# A-Headers.net
KiCad netlist of a schematic drawn in Altium Designer
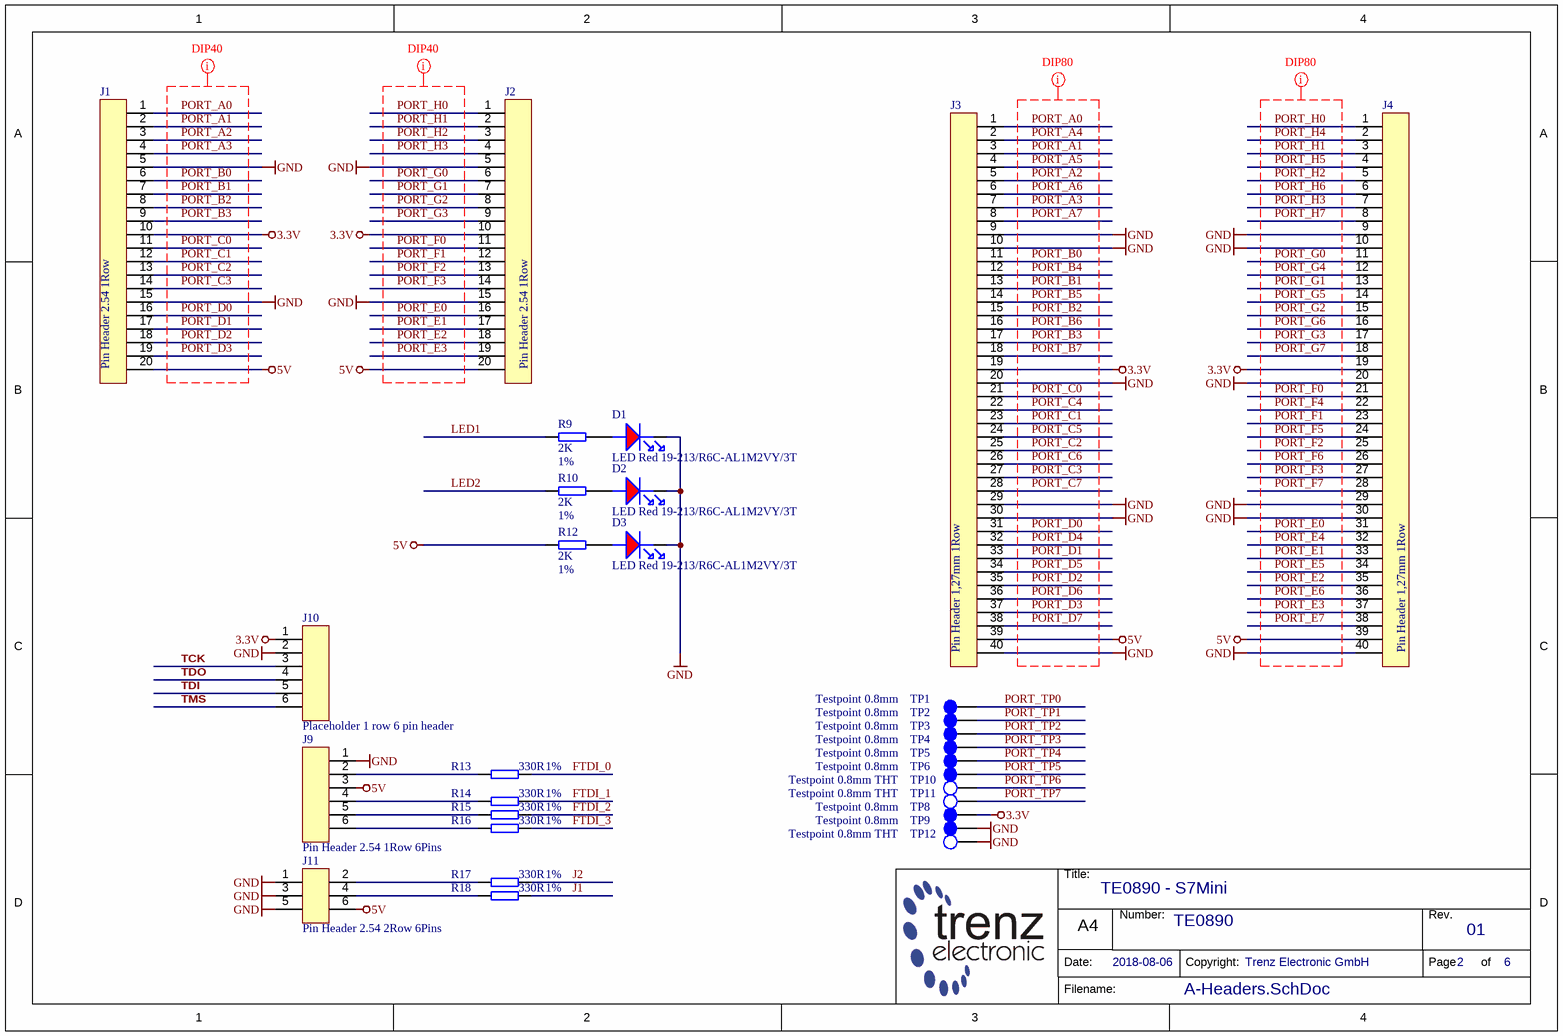
[diagram p0: A-Headers.SchDoc]

(export (version "E")
  (design (tool "Eeschema 10.0.6"))
  (components
    (comp (ref "D1")
      (value "LED Red 19-213/R6C-AL1M2VY/3T")
      (footprint "LEDC1608X55N_RED")
      (description "Chip LED 0603 Briliant Red")
      (libsource (lib "TE") (part "LED_ROT"))
    )
    (comp (ref "D2")
      (value "LED Red 19-213/R6C-AL1M2VY/3T")
      (footprint "LEDC1608X55N_RED")
      (description "Chip LED 0603 Briliant Red")
      (libsource (lib "TE") (part "LED_ROT"))
    )
    (comp (ref "D3")
      (value "LED Red 19-213/R6C-AL1M2VY/3T")
      (footprint "LEDC1608X55N_RED")
      (description "Chip LED 0603 Briliant Red")
      (libsource (lib "TE") (part "LED_ROT"))
    )
    (comp (ref "J1")
      (value "Pin Header 2.54 1Row")
      (footprint "STIFTLEISTE2_54 OG 1R-20")
      (description "Stiftleiste versetzt 1-reihig, 20pol.")
      (libsource (lib "") (part "CON-20_1"))
    )
    (comp (ref "J2")
      (value "Pin Header 2.54 1Row")
      (footprint "STIFTLEISTE2_54 OG 1R-20")
      (description "Stiftleiste versetzt 1-reihig, 20pol.")
      (libsource (lib "TE") (part "CON-20"))
    )
    (comp (ref "J3")
      (value "Pin Header 1,27mm 1Row")
      (footprint "STIFTLEISTE1_27 OG 1R-40")
      (description "Stiftleiste versetzt 1-reihig, 40pol.")
      (libsource (lib "") (part "CON-40_1"))
    )
    (comp (ref "J4")
      (value "Pin Header 1,27mm 1Row")
      (footprint "STIFTLEISTE1_27 OG 1R-40")
      (description "Stiftleiste versetzt 1-reihig, 40pol.")
      (libsource (lib "TE") (part "CON-40"))
    )
    (comp (ref "J9")
      (value "Pin Header 2.54 1Row 6Pins")
      (footprint "STIFTLEISTE2_54 OG 1R-6")
      (description "Stiftleiste gerade 1-reihig, 6pol")
      (libsource (lib "") (part "CON-6_1"))
    )
    (comp (ref "J10")
      (value "Placeholder 1 row 6 pin header")
      (footprint "STIFTLEISTE2_54 OG 1R-6V")
      (description "Stiftleiste versetzt 1-reihig, 6pol.")
      (libsource (lib "TE") (part "STIFTLEISTE2_54 OG 1R-6V"))
    )
    (comp (ref "J11")
      (value "Pin Header 2.54 2Row 6Pins")
      (footprint "STIFTLEISTE2_54 OG 2R-6")
      (description "Stiftleiste gerade 2-reihig, 6pol.")
      (libsource (lib "TE") (part "CON-6"))
    )
    (comp (ref "R9")
      (value "2K")
      (footprint "RESC1005X40N")
      (description "WID SMD 2K 1% 0,063W")
      (fields (field (name "TOLERANCE") "1%"))
      (libsource (lib "TE") (part "RES"))
    )
    (comp (ref "R10")
      (value "2K")
      (footprint "RESC1005X40N")
      (description "WID SMD 2K 1% 0,063W")
      (fields (field (name "TOLERANCE") "1%"))
      (libsource (lib "TE") (part "RES"))
    )
    (comp (ref "R12")
      (value "2K")
      (footprint "RESC1005X40N")
      (description "WID SMD 2K 1% 0,063W")
      (fields (field (name "TOLERANCE") "1%"))
      (libsource (lib "TE") (part "RES"))
    )
    (comp (ref "R13")
      (value "330R")
      (footprint "RESC1005X40N")
      (description "WID SMD 330R 1% 0,063W  BF 1005 (0402)")
      (fields (field (name "TOLERANCE") "1%"))
      (libsource (lib "TE") (part "RES"))
    )
    (comp (ref "R14")
      (value "330R")
      (footprint "RESC1005X40N")
      (description "WID SMD 330R 1% 0,063W  BF 1005 (0402)")
      (fields (field (name "TOLERANCE") "1%"))
      (libsource (lib "TE") (part "RES"))
    )
    (comp (ref "R15")
      (value "330R")
      (footprint "RESC1005X40N")
      (description "WID SMD 330R 1% 0,063W  BF 1005 (0402)")
      (fields (field (name "TOLERANCE") "1%"))
      (libsource (lib "TE") (part "RES"))
    )
    (comp (ref "R16")
      (value "330R")
      (footprint "RESC1005X40N")
      (description "WID SMD 330R 1% 0,063W  BF 1005 (0402)")
      (fields (field (name "TOLERANCE") "1%"))
      (libsource (lib "TE") (part "RES"))
    )
    (comp (ref "R17")
      (value "330R")
      (footprint "RESC1005X40N")
      (description "WID SMD 330R 1% 0,063W  BF 1005 (0402)")
      (fields (field (name "TOLERANCE") "1%"))
      (libsource (lib "TE") (part "RES"))
    )
    (comp (ref "R18")
      (value "330R")
      (footprint "RESC1005X40N")
      (description "WID SMD 330R 1% 0,063W  BF 1005 (0402)")
      (fields (field (name "TOLERANCE") "1%"))
      (libsource (lib "TE") (part "RES"))
    )
    (comp (ref "TP1") (value "Testpoint 0.8mm") (footprint "TP_0.8mm") (libsource (lib "TE") (part "TP")))
    (comp (ref "TP2") (value "Testpoint 0.8mm") (footprint "TP_0.8mm") (libsource (lib "TE") (part "TP")))
    (comp (ref "TP3") (value "Testpoint 0.8mm") (footprint "TP_0.8mm") (libsource (lib "TE") (part "TP")))
    (comp (ref "TP4") (value "Testpoint 0.8mm") (footprint "TP_0.8mm") (libsource (lib "TE") (part "TP")))
    (comp (ref "TP5") (value "Testpoint 0.8mm") (footprint "TP_0.8mm") (libsource (lib "TE") (part "TP")))
    (comp (ref "TP6") (value "Testpoint 0.8mm") (footprint "TP_0.8mm") (libsource (lib "TE") (part "TP")))
    (comp (ref "TP8") (value "Testpoint 0.8mm") (footprint "TP_0.8mm") (libsource (lib "TE") (part "TP")))
    (comp (ref "TP9") (value "Testpoint 0.8mm") (footprint "TP_0.8mm") (libsource (lib "TE") (part "TP")))
    (comp (ref "TP10")
      (value "Testpoint 0.8mm THT")
      (footprint "TP_0.8mm_THT")
      (description "Testpoint 0.8mm TH")
      (libsource (lib "TE") (part "TP_THT"))
    )
    (comp (ref "TP11")
      (value "Testpoint 0.8mm THT")
      (footprint "TP_0.8mm_THT")
      (description "Testpoint 0.8mm TH")
      (libsource (lib "TE") (part "TP_THT"))
    )
    (comp (ref "TP12")
      (value "Testpoint 0.8mm THT")
      (footprint "TP_0.8mm_THT")
      (description "Testpoint 0.8mm TH")
      (libsource (lib "TE") (part "TP_THT"))
    )
  )
  (nets
    (net (code "1") (name "/FTDI_0") (class "Default")
      (node (ref "R13") (pin "2") (pinfunction "2_2") (pintype "passive"))
    )
    (net (code "2") (name "/FTDI_1") (class "Default")
      (node (ref "R14") (pin "2") (pinfunction "2_2") (pintype "passive"))
    )
    (net (code "3") (name "/FTDI_2") (class "Default")
      (node (ref "R15") (pin "2") (pinfunction "2_2") (pintype "passive"))
    )
    (net (code "4") (name "/FTDI_3") (class "Default")
      (node (ref "R16") (pin "2") (pinfunction "2_2") (pintype "passive"))
    )
    (net (code "5") (name "/J1") (class "Default")
      (node (ref "R18") (pin "2") (pinfunction "2_2") (pintype "passive"))
    )
    (net (code "6") (name "/J2") (class "Default")
      (node (ref "R17") (pin "2") (pinfunction "2_2") (pintype "passive"))
    )
    (net (code "7") (name "/LED1") (class "Default")
      (node (ref "R9") (pin "1") (pinfunction "1_1") (pintype "passive"))
    )
    (net (code "8") (name "/LED2") (class "Default")
      (node (ref "R10") (pin "1") (pinfunction "1_1") (pintype "passive"))
    )
    (net (code "9") (name "/PORT_A0") (class "Default")
      (node (ref "J1") (pin "1") (pinfunction "1_1") (pintype "passive"))
      (node (ref "J3") (pin "1") (pinfunction "1_1") (pintype "passive"))
    )
    (net (code "10") (name "/PORT_A1") (class "Default")
      (node (ref "J1") (pin "2") (pinfunction "2_2") (pintype "passive"))
      (node (ref "J3") (pin "3") (pinfunction "3_3") (pintype "passive"))
    )
    (net (code "11") (name "/PORT_A2") (class "Default")
      (node (ref "J1") (pin "3") (pinfunction "3_3") (pintype "passive"))
      (node (ref "J3") (pin "5") (pinfunction "5_5") (pintype "passive"))
    )
    (net (code "12") (name "/PORT_A3") (class "Default")
      (node (ref "J1") (pin "4") (pinfunction "4_4") (pintype "passive"))
      (node (ref "J3") (pin "7") (pinfunction "7_7") (pintype "passive"))
    )
    (net (code "13") (name "/PORT_A4") (class "Default")
      (node (ref "J3") (pin "2") (pinfunction "2_2") (pintype "passive"))
    )
    (net (code "14") (name "/PORT_A5") (class "Default")
      (node (ref "J3") (pin "4") (pinfunction "4_4") (pintype "passive"))
    )
    (net (code "15") (name "/PORT_A6") (class "Default")
      (node (ref "J3") (pin "6") (pinfunction "6_6") (pintype "passive"))
    )
    (net (code "16") (name "/PORT_A7") (class "Default")
      (node (ref "J3") (pin "8") (pinfunction "8_8") (pintype "passive"))
    )
    (net (code "17") (name "/PORT_B0") (class "Default")
      (node (ref "J1") (pin "6") (pinfunction "6_6") (pintype "passive"))
      (node (ref "J3") (pin "11") (pinfunction "11_11") (pintype "passive"))
    )
    (net (code "18") (name "/PORT_B1") (class "Default")
      (node (ref "J1") (pin "7") (pinfunction "7_7") (pintype "passive"))
      (node (ref "J3") (pin "13") (pinfunction "13_13") (pintype "passive"))
    )
    (net (code "19") (name "/PORT_B2") (class "Default")
      (node (ref "J1") (pin "8") (pinfunction "8_8") (pintype "passive"))
      (node (ref "J3") (pin "15") (pinfunction "15_15") (pintype "passive"))
    )
    (net (code "20") (name "/PORT_B3") (class "Default")
      (node (ref "J1") (pin "9") (pinfunction "9_9") (pintype "passive"))
      (node (ref "J3") (pin "17") (pinfunction "17_17") (pintype "passive"))
    )
    (net (code "21") (name "/PORT_B4") (class "Default")
      (node (ref "J3") (pin "12") (pinfunction "12_12") (pintype "passive"))
    )
    (net (code "22") (name "/PORT_B5") (class "Default")
      (node (ref "J3") (pin "14") (pinfunction "14_14") (pintype "passive"))
    )
    (net (code "23") (name "/PORT_B6") (class "Default")
      (node (ref "J3") (pin "16") (pinfunction "16_16") (pintype "passive"))
    )
    (net (code "24") (name "/PORT_B7") (class "Default")
      (node (ref "J3") (pin "18") (pinfunction "18_18") (pintype "passive"))
    )
    (net (code "25") (name "/PORT_C0") (class "Default")
      (node (ref "J1") (pin "11") (pinfunction "11_11") (pintype "passive"))
      (node (ref "J3") (pin "21") (pinfunction "21_21") (pintype "passive"))
    )
    (net (code "26") (name "/PORT_C1") (class "Default")
      (node (ref "J1") (pin "12") (pinfunction "12_12") (pintype "passive"))
      (node (ref "J3") (pin "23") (pinfunction "23_23") (pintype "passive"))
    )
    (net (code "27") (name "/PORT_C2") (class "Default")
      (node (ref "J1") (pin "13") (pinfunction "13_13") (pintype "passive"))
      (node (ref "J3") (pin "25") (pinfunction "25_25") (pintype "passive"))
    )
    (net (code "28") (name "/PORT_C3") (class "Default")
      (node (ref "J1") (pin "14") (pinfunction "14_14") (pintype "passive"))
      (node (ref "J3") (pin "27") (pinfunction "27_27") (pintype "passive"))
    )
    (net (code "29") (name "/PORT_C4") (class "Default")
      (node (ref "J3") (pin "22") (pinfunction "22_22") (pintype "passive"))
    )
    (net (code "30") (name "/PORT_C5") (class "Default")
      (node (ref "J3") (pin "24") (pinfunction "24_24") (pintype "passive"))
    )
    (net (code "31") (name "/PORT_C6") (class "Default")
      (node (ref "J3") (pin "26") (pinfunction "26_26") (pintype "passive"))
    )
    (net (code "32") (name "/PORT_C7") (class "Default")
      (node (ref "J3") (pin "28") (pinfunction "28_28") (pintype "passive"))
    )
    (net (code "33") (name "/PORT_D0") (class "Default")
      (node (ref "J1") (pin "16") (pinfunction "16_16") (pintype "passive"))
      (node (ref "J3") (pin "31") (pinfunction "31_31") (pintype "passive"))
    )
    (net (code "34") (name "/PORT_D1") (class "Default")
      (node (ref "J1") (pin "17") (pinfunction "17_17") (pintype "passive"))
      (node (ref "J3") (pin "33") (pinfunction "33_33") (pintype "passive"))
    )
    (net (code "35") (name "/PORT_D2") (class "Default")
      (node (ref "J1") (pin "18") (pinfunction "18_18") (pintype "passive"))
      (node (ref "J3") (pin "35") (pinfunction "35_35") (pintype "passive"))
    )
    (net (code "36") (name "/PORT_D3") (class "Default")
      (node (ref "J1") (pin "19") (pinfunction "19_19") (pintype "passive"))
      (node (ref "J3") (pin "37") (pinfunction "37_37") (pintype "passive"))
    )
    (net (code "37") (name "/PORT_D4") (class "Default")
      (node (ref "J3") (pin "32") (pinfunction "32_32") (pintype "passive"))
    )
    (net (code "38") (name "/PORT_D5") (class "Default")
      (node (ref "J3") (pin "34") (pinfunction "34_34") (pintype "passive"))
    )
    (net (code "39") (name "/PORT_D6") (class "Default")
      (node (ref "J3") (pin "36") (pinfunction "36_36") (pintype "passive"))
    )
    (net (code "40") (name "/PORT_D7") (class "Default")
      (node (ref "J3") (pin "38") (pinfunction "38_38") (pintype "passive"))
    )
    (net (code "41") (name "/PORT_E0") (class "Default")
      (node (ref "J2") (pin "16") (pinfunction "16_16") (pintype "passive"))
      (node (ref "J4") (pin "31") (pinfunction "31_31") (pintype "passive"))
    )
    (net (code "42") (name "/PORT_E1") (class "Default")
      (node (ref "J2") (pin "17") (pinfunction "17_17") (pintype "passive"))
      (node (ref "J4") (pin "33") (pinfunction "33_33") (pintype "passive"))
    )
    (net (code "43") (name "/PORT_E2") (class "Default")
      (node (ref "J2") (pin "18") (pinfunction "18_18") (pintype "passive"))
      (node (ref "J4") (pin "35") (pinfunction "35_35") (pintype "passive"))
    )
    (net (code "44") (name "/PORT_E3") (class "Default")
      (node (ref "J2") (pin "19") (pinfunction "19_19") (pintype "passive"))
      (node (ref "J4") (pin "37") (pinfunction "37_37") (pintype "passive"))
    )
    (net (code "45") (name "/PORT_E4") (class "Default")
      (node (ref "J4") (pin "32") (pinfunction "32_32") (pintype "passive"))
    )
    (net (code "46") (name "/PORT_E5") (class "Default")
      (node (ref "J4") (pin "34") (pinfunction "34_34") (pintype "passive"))
    )
    (net (code "47") (name "/PORT_E6") (class "Default")
      (node (ref "J4") (pin "36") (pinfunction "36_36") (pintype "passive"))
    )
    (net (code "48") (name "/PORT_E7") (class "Default")
      (node (ref "J4") (pin "38") (pinfunction "38_38") (pintype "passive"))
    )
    (net (code "49") (name "/PORT_F0") (class "Default")
      (node (ref "J2") (pin "11") (pinfunction "11_11") (pintype "passive"))
      (node (ref "J4") (pin "21") (pinfunction "21_21") (pintype "passive"))
    )
    (net (code "50") (name "/PORT_F1") (class "Default")
      (node (ref "J2") (pin "12") (pinfunction "12_12") (pintype "passive"))
      (node (ref "J4") (pin "23") (pinfunction "23_23") (pintype "passive"))
    )
    (net (code "51") (name "/PORT_F2") (class "Default")
      (node (ref "J2") (pin "13") (pinfunction "13_13") (pintype "passive"))
      (node (ref "J4") (pin "25") (pinfunction "25_25") (pintype "passive"))
    )
    (net (code "52") (name "/PORT_F3") (class "Default")
      (node (ref "J2") (pin "14") (pinfunction "14_14") (pintype "passive"))
      (node (ref "J4") (pin "27") (pinfunction "27_27") (pintype "passive"))
    )
    (net (code "53") (name "/PORT_F4") (class "Default")
      (node (ref "J4") (pin "22") (pinfunction "22_22") (pintype "passive"))
    )
    (net (code "54") (name "/PORT_F5") (class "Default")
      (node (ref "J4") (pin "24") (pinfunction "24_24") (pintype "passive"))
    )
    (net (code "55") (name "/PORT_F6") (class "Default")
      (node (ref "J4") (pin "26") (pinfunction "26_26") (pintype "passive"))
    )
    (net (code "56") (name "/PORT_F7") (class "Default")
      (node (ref "J4") (pin "28") (pinfunction "28_28") (pintype "passive"))
    )
    (net (code "57") (name "/PORT_G0") (class "Default")
      (node (ref "J2") (pin "6") (pinfunction "6_6") (pintype "passive"))
      (node (ref "J4") (pin "11") (pinfunction "11_11") (pintype "passive"))
    )
    (net (code "58") (name "/PORT_G1") (class "Default")
      (node (ref "J2") (pin "7") (pinfunction "7_7") (pintype "passive"))
      (node (ref "J4") (pin "13") (pinfunction "13_13") (pintype "passive"))
    )
    (net (code "59") (name "/PORT_G2") (class "Default")
      (node (ref "J2") (pin "8") (pinfunction "8_8") (pintype "passive"))
      (node (ref "J4") (pin "15") (pinfunction "15_15") (pintype "passive"))
    )
    (net (code "60") (name "/PORT_G3") (class "Default")
      (node (ref "J2") (pin "9") (pinfunction "9_9") (pintype "passive"))
      (node (ref "J4") (pin "17") (pinfunction "17_17") (pintype "passive"))
    )
    (net (code "61") (name "/PORT_G4") (class "Default")
      (node (ref "J4") (pin "12") (pinfunction "12_12") (pintype "passive"))
    )
    (net (code "62") (name "/PORT_G5") (class "Default")
      (node (ref "J4") (pin "14") (pinfunction "14_14") (pintype "passive"))
    )
    (net (code "63") (name "/PORT_G6") (class "Default")
      (node (ref "J4") (pin "16") (pinfunction "16_16") (pintype "passive"))
    )
    (net (code "64") (name "/PORT_G7") (class "Default")
      (node (ref "J4") (pin "18") (pinfunction "18_18") (pintype "passive"))
    )
    (net (code "65") (name "/PORT_H0") (class "Default")
      (node (ref "J2") (pin "1") (pinfunction "1_1") (pintype "passive"))
      (node (ref "J4") (pin "1") (pinfunction "1_1") (pintype "passive"))
    )
    (net (code "66") (name "/PORT_H1") (class "Default")
      (node (ref "J2") (pin "2") (pinfunction "2_2") (pintype "passive"))
      (node (ref "J4") (pin "3") (pinfunction "3_3") (pintype "passive"))
    )
    (net (code "67") (name "/PORT_H2") (class "Default")
      (node (ref "J2") (pin "3") (pinfunction "3_3") (pintype "passive"))
      (node (ref "J4") (pin "5") (pinfunction "5_5") (pintype "passive"))
    )
    (net (code "68") (name "/PORT_H3") (class "Default")
      (node (ref "J2") (pin "4") (pinfunction "4_4") (pintype "passive"))
      (node (ref "J4") (pin "7") (pinfunction "7_7") (pintype "passive"))
    )
    (net (code "69") (name "/PORT_H4") (class "Default")
      (node (ref "J4") (pin "2") (pinfunction "2_2") (pintype "passive"))
    )
    (net (code "70") (name "/PORT_H5") (class "Default")
      (node (ref "J4") (pin "4") (pinfunction "4_4") (pintype "passive"))
    )
    (net (code "71") (name "/PORT_H6") (class "Default")
      (node (ref "J4") (pin "6") (pinfunction "6_6") (pintype "passive"))
    )
    (net (code "72") (name "/PORT_H7") (class "Default")
      (node (ref "J4") (pin "8") (pinfunction "8_8") (pintype "passive"))
    )
    (net (code "73") (name "/PORT_TP0") (class "Default") (node (ref "TP1") (pin "1") (pintype "passive")))
    (net (code "74") (name "/PORT_TP1") (class "Default") (node (ref "TP2") (pin "1") (pintype "passive")))
    (net (code "75") (name "/PORT_TP2") (class "Default") (node (ref "TP3") (pin "1") (pintype "passive")))
    (net (code "76") (name "/PORT_TP3") (class "Default") (node (ref "TP4") (pin "1") (pintype "passive")))
    (net (code "77") (name "/PORT_TP4") (class "Default") (node (ref "TP5") (pin "1") (pintype "passive")))
    (net (code "78") (name "/PORT_TP5") (class "Default") (node (ref "TP6") (pin "1") (pintype "passive")))
    (net (code "79") (name "/PORT_TP6") (class "Default") (node (ref "TP10") (pin "1") (pintype "passive")))
    (net (code "80") (name "/PORT_TP7") (class "Default") (node (ref "TP11") (pin "1") (pintype "passive")))
    (net (code "81") (name "/TCK") (class "Default")
      (node (ref "J10") (pin "3") (pinfunction "3_3") (pintype "passive"))
    )
    (net (code "82") (name "/TDI") (class "Default")
      (node (ref "J10") (pin "5") (pinfunction "5_5") (pintype "passive"))
    )
    (net (code "83") (name "/TDO") (class "Default")
      (node (ref "J10") (pin "4") (pinfunction "4_4") (pintype "passive"))
    )
    (net (code "84") (name "/TMS") (class "Default")
      (node (ref "J10") (pin "6") (pinfunction "6_6") (pintype "passive"))
    )
    (net (code "85") (name "3.3V") (class "Default")
      (node (ref "J1") (pin "10") (pinfunction "10_10") (pintype "passive"))
      (node (ref "J10") (pin "1") (pinfunction "1_1") (pintype "passive"))
      (node (ref "J2") (pin "10") (pinfunction "10_10") (pintype "passive"))
      (node (ref "J3") (pin "19") (pinfunction "19_19") (pintype "passive"))
      (node (ref "J4") (pin "19") (pinfunction "19_19") (pintype "passive"))
      (node (ref "TP8") (pin "1") (pintype "passive"))
    )
    (net (code "86") (name "5V") (class "Default")
      (node (ref "J1") (pin "20") (pinfunction "20_20") (pintype "passive"))
      (node (ref "J11") (pin "6") (pintype "passive"))
      (node (ref "J2") (pin "20") (pinfunction "20_20") (pintype "passive"))
      (node (ref "J3") (pin "39") (pinfunction "39_39") (pintype "passive"))
      (node (ref "J4") (pin "39") (pinfunction "39_39") (pintype "passive"))
      (node (ref "J9") (pin "3") (pintype "passive"))
      (node (ref "R12") (pin "1") (pinfunction "1_1") (pintype "passive"))
    )
    (net (code "87") (name "GND") (class "Default")
      (node (ref "D1") (pin "K") (pinfunction "K_K") (pintype "passive"))
      (node (ref "D2") (pin "K") (pinfunction "K_K") (pintype "passive"))
      (node (ref "D3") (pin "K") (pinfunction "K_K") (pintype "passive"))
      (node (ref "J1") (pin "15") (pinfunction "15_15") (pintype "passive"))
      (node (ref "J1") (pin "5") (pinfunction "5_5") (pintype "passive"))
      (node (ref "J10") (pin "2") (pinfunction "2_2") (pintype "passive"))
      (node (ref "J11") (pin "1") (pintype "passive"))
      (node (ref "J11") (pin "3") (pintype "passive"))
      (node (ref "J11") (pin "5") (pintype "passive"))
      (node (ref "J2") (pin "15") (pinfunction "15_15") (pintype "passive"))
      (node (ref "J2") (pin "5") (pinfunction "5_5") (pintype "passive"))
      (node (ref "J3") (pin "10") (pinfunction "10_10") (pintype "passive"))
      (node (ref "J3") (pin "20") (pinfunction "20_20") (pintype "passive"))
      (node (ref "J3") (pin "29") (pinfunction "29_29") (pintype "passive"))
      (node (ref "J3") (pin "30") (pinfunction "30_30") (pintype "passive"))
      (node (ref "J3") (pin "40") (pinfunction "40_40") (pintype "passive"))
      (node (ref "J3") (pin "9") (pinfunction "9_9") (pintype "passive"))
      (node (ref "J4") (pin "10") (pinfunction "10_10") (pintype "passive"))
      (node (ref "J4") (pin "20") (pinfunction "20_20") (pintype "passive"))
      (node (ref "J4") (pin "29") (pinfunction "29_29") (pintype "passive"))
      (node (ref "J4") (pin "30") (pinfunction "30_30") (pintype "passive"))
      (node (ref "J4") (pin "40") (pinfunction "40_40") (pintype "passive"))
      (node (ref "J4") (pin "9") (pinfunction "9_9") (pintype "passive"))
      (node (ref "J9") (pin "1") (pintype "passive"))
      (node (ref "TP12") (pin "1") (pintype "passive"))
      (node (ref "TP9") (pin "1") (pintype "passive"))
    )
    (net (code "88") (name "Net-(D1-PadA)") (class "Default")
      (node (ref "D1") (pin "A") (pinfunction "A_A") (pintype "passive"))
      (node (ref "R9") (pin "2") (pinfunction "2_2") (pintype "passive"))
    )
    (net (code "89") (name "Net-(D2-PadA)") (class "Default")
      (node (ref "D2") (pin "A") (pinfunction "A_A") (pintype "passive"))
      (node (ref "R10") (pin "2") (pinfunction "2_2") (pintype "passive"))
    )
    (net (code "90") (name "Net-(D3-PadA)") (class "Default")
      (node (ref "D3") (pin "A") (pinfunction "A_A") (pintype "passive"))
      (node (ref "R12") (pin "2") (pinfunction "2_2") (pintype "passive"))
    )
    (net (code "91") (name "Net-(J9-Pad2)") (class "Default")
      (node (ref "J9") (pin "2") (pintype "passive"))
      (node (ref "R13") (pin "1") (pinfunction "1_1") (pintype "passive"))
    )
    (net (code "92") (name "Net-(J9-Pad4)") (class "Default")
      (node (ref "J9") (pin "4") (pintype "passive"))
      (node (ref "R14") (pin "1") (pinfunction "1_1") (pintype "passive"))
    )
    (net (code "93") (name "Net-(J9-Pad5)") (class "Default")
      (node (ref "J9") (pin "5") (pintype "passive"))
      (node (ref "R15") (pin "1") (pinfunction "1_1") (pintype "passive"))
    )
    (net (code "94") (name "Net-(J9-Pad6)") (class "Default")
      (node (ref "J9") (pin "6") (pintype "passive"))
      (node (ref "R16") (pin "1") (pinfunction "1_1") (pintype "passive"))
    )
    (net (code "95") (name "Net-(J11-Pad2)") (class "Default")
      (node (ref "J11") (pin "2") (pintype "passive"))
      (node (ref "R17") (pin "1") (pinfunction "1_1") (pintype "passive"))
    )
    (net (code "96") (name "Net-(J11-Pad4)") (class "Default")
      (node (ref "J11") (pin "4") (pintype "passive"))
      (node (ref "R18") (pin "1") (pinfunction "1_1") (pintype "passive"))
    )
  )
)
